# Dental_Support.net
KiCad netlist of a schematic drawn in Altium Designer
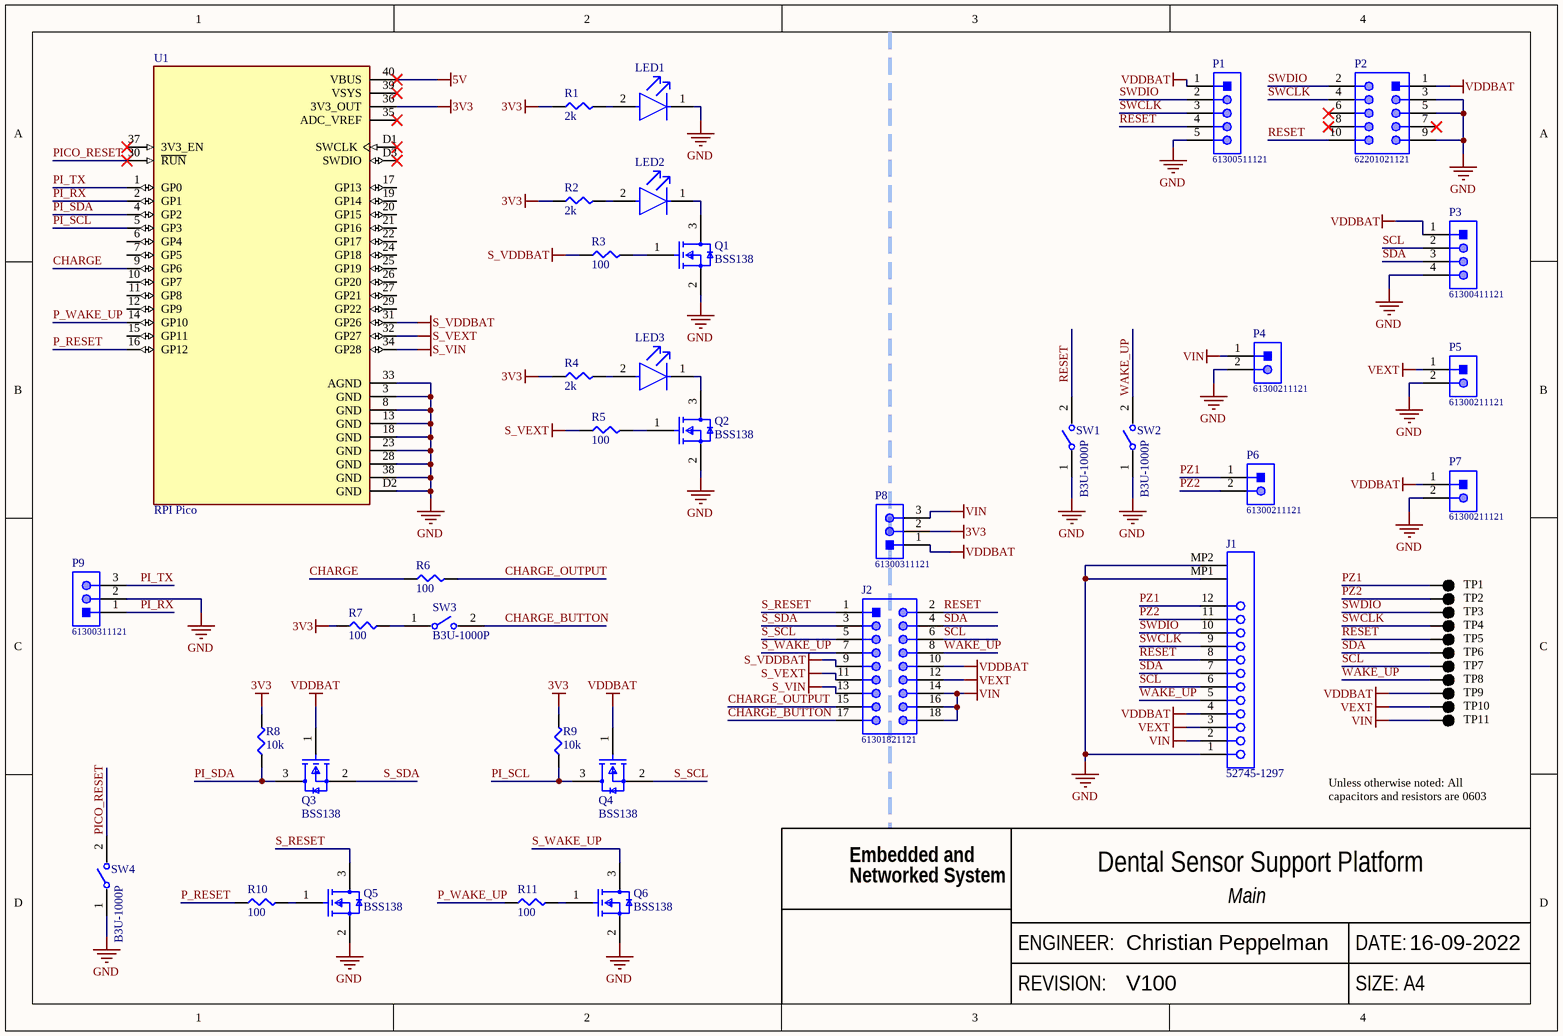
[diagram p0: Dental Support.SchDoc]

(export (version "E")
  (design (tool "Eeschema 10.0.6"))
  (components
    (comp (ref "J1")
      (value "52745-1297")
      (footprint "MOLX-52745-1297")
      (fields (field (name "MANUFACTURER") "Molex"))
      (libsource (lib "Altium Content Vault") (part "MOLX-52745-1297"))
    )
    (comp (ref "J2")
      (value "61301821121")
      (footprint "61301821121")
      (description "THT Vertical Pin Header WR-PHD, Pitch 2.54 mm, Dual Row, 18 pins")
      (fields (field (name "MANUFACTURER") "Wurth Elektronik") (field (name "PUBLISHER") "WurthElektronik"))
      (libsource (lib "Altium Content Vault") (part "WE-CN-2P-M-R18"))
    )
    (comp (ref "LED1")
      (value "150080SS75000")
      (footprint "FP-150080SS75000-MFG")
      (description "LED RED CLEAR 0805 SMD")
      (libsource (lib "Altium Content Vault") (part "8706943c75ba83719d021d2fdc84c58"))
    )
    (comp (ref "LED2")
      (value "150080SS75000")
      (footprint "FP-150080SS75000-MFG")
      (description "LED RED CLEAR 0805 SMD")
      (libsource (lib "Altium Content Vault") (part "8706943c75ba83719d021d2fdc84c58"))
    )
    (comp (ref "LED3")
      (value "150080SS75000")
      (footprint "FP-150080SS75000-MFG")
      (description "LED RED CLEAR 0805 SMD")
      (libsource (lib "Altium Content Vault") (part "8706943c75ba83719d021d2fdc84c58"))
    )
    (comp (ref "P1")
      (value "61300511121")
      (footprint "61300511121")
      (description "THT Vertical Pin Header WR-PHD, Pitch 2.54 mm, Single Row, 5 pins")
      (fields (field (name "MANUFACTURER") "Wurth Elektronik") (field (name "PUBLISHER") "WurthElektronik"))
      (libsource (lib "Altium Content Vault") (part "WE-CN-1P-M-R5"))
    )
    (comp (ref "P2")
      (value "62201021121")
      (footprint "62201021121")
      (description "THT Vertical Pin Header WR-PHD, Pitch 1.27 mm, Dual Row, 10 pins")
      (fields (field (name "MANUFACTURER") "Wurth Elektronik") (field (name "PUBLISHER") "WurthElektronik"))
      (libsource (lib "Altium Content Vault") (part "WE-CN-2P-M-R10"))
    )
    (comp (ref "P3")
      (value "61300411121")
      (footprint "61300411121")
      (description "THT Vertical Pin Header WR-PHD, Pitch 2.54 mm, Single Row, 4 pins")
      (fields (field (name "MANUFACTURER") "Wurth Elektronik") (field (name "PUBLISHER") "WurthElektronik"))
      (libsource (lib "Altium Content Vault") (part "WE-CN-1P-M-R4"))
    )
    (comp (ref "P4")
      (value "61300211121")
      (footprint "61300211121")
      (description "THT Vertical Pin Header WR-PHD, Pitch 2.54 mm, Single Row, 2 pins")
      (fields (field (name "MANUFACTURER") "Wurth Elektronik") (field (name "PUBLISHER") "WurthElektronik"))
      (libsource (lib "Altium Content Vault") (part "WE-CN-1P-M-R2"))
    )
    (comp (ref "P5")
      (value "61300211121")
      (footprint "61300211121")
      (description "THT Vertical Pin Header WR-PHD, Pitch 2.54 mm, Single Row, 2 pins")
      (fields (field (name "MANUFACTURER") "Wurth Elektronik") (field (name "PUBLISHER") "WurthElektronik"))
      (libsource (lib "Altium Content Vault") (part "WE-CN-1P-M-R2"))
    )
    (comp (ref "P6")
      (value "61300211121")
      (footprint "61300211121")
      (description "THT Vertical Pin Header WR-PHD, Pitch 2.54 mm, Single Row, 2 pins")
      (fields (field (name "MANUFACTURER") "Wurth Elektronik") (field (name "PUBLISHER") "WurthElektronik"))
      (libsource (lib "Altium Content Vault") (part "WE-CN-1P-M-R2"))
    )
    (comp (ref "P7")
      (value "61300211121")
      (footprint "61300211121")
      (description "THT Vertical Pin Header WR-PHD, Pitch 2.54 mm, Single Row, 2 pins")
      (fields (field (name "MANUFACTURER") "Wurth Elektronik") (field (name "PUBLISHER") "WurthElektronik"))
      (libsource (lib "Altium Content Vault") (part "WE-CN-1P-M-R2"))
    )
    (comp (ref "P8")
      (value "61300311121")
      (footprint "61300311121")
      (description "THT Vertical Pin Header WR-PHD, Pitch 2.54 mm, Single Row, 3 pins")
      (fields (field (name "MANUFACTURER") "Wurth Elektronik") (field (name "PUBLISHER") "WurthElektronik"))
      (libsource (lib "Altium Content Vault") (part "WE-CN-1P-M-R3"))
    )
    (comp (ref "P9")
      (value "61300311121")
      (footprint "61300311121")
      (description "THT Vertical Pin Header WR-PHD, Pitch 2.54 mm, Single Row, 3 pins")
      (fields (field (name "MANUFACTURER") "Wurth Elektronik") (field (name "PUBLISHER") "WurthElektronik"))
      (libsource (lib "Altium Content Vault") (part "WE-CN-1P-M-R3"))
    )
    (comp (ref "Q1")
      (value "BSS138")
      (footprint "FP-318-08-IPC_B")
      (description "MOSFET N-CH 50V 220MA SOT-23")
      (libsource (lib "Altium Content Vault") (part "3b9c635fedb024a5347a57b145af9cc"))
    )
    (comp (ref "Q2")
      (value "BSS138")
      (footprint "FP-318-08-IPC_B")
      (description "MOSFET N-CH 50V 220MA SOT-23")
      (libsource (lib "Altium Content Vault") (part "3b9c635fedb024a5347a57b145af9cc"))
    )
    (comp (ref "Q3")
      (value "BSS138")
      (footprint "FP-318-08-IPC_B")
      (description "MOSFET N-CH 50V 220MA SOT-23")
      (libsource (lib "Altium Content Vault") (part "3b9c635fedb024a5347a57b145af9cc"))
    )
    (comp (ref "Q4")
      (value "BSS138")
      (footprint "FP-318-08-IPC_B")
      (description "MOSFET N-CH 50V 220MA SOT-23")
      (libsource (lib "Altium Content Vault") (part "3b9c635fedb024a5347a57b145af9cc"))
    )
    (comp (ref "Q5")
      (value "BSS138")
      (footprint "FP-318-08-IPC_B")
      (description "MOSFET N-CH 50V 220MA SOT-23")
      (libsource (lib "Altium Content Vault") (part "3b9c635fedb024a5347a57b145af9cc"))
    )
    (comp (ref "Q6")
      (value "BSS138")
      (footprint "FP-318-08-IPC_B")
      (description "MOSFET N-CH 50V 220MA SOT-23")
      (libsource (lib "Altium Content Vault") (part "3b9c635fedb024a5347a57b145af9cc"))
    )
    (comp (ref "R1")
      (value "2k")
      (footprint "RESC2012X06N")
      (description "RES SMD 2K OHM 1% 1/8W 0805")
      (fields
        (field (name "PART NUMBER") "ERJ-6ENF2001V")
        (field (name "DIGI-KEY PART NUMBER") "P2.00KCCT-ND")
      )
      (libsource (lib "Panasonic_ERJ_0805") (part "ERJ-6ENF2001V"))
    )
    (comp (ref "R2")
      (value "2k")
      (footprint "RESC2012X06N")
      (description "RES SMD 2K OHM 1% 1/8W 0805")
      (fields
        (field (name "PART NUMBER") "ERJ-6ENF2001V")
        (field (name "DIGI-KEY PART NUMBER") "P2.00KCCT-ND")
      )
      (libsource (lib "Panasonic_ERJ_0805") (part "ERJ-6ENF2001V"))
    )
    (comp (ref "R3")
      (value "100")
      (footprint "RESC2012X06N")
      (description "RES SMD 100 OHM 1% 1/8W 0805")
      (fields (field (name "PART NUMBER") "ERJ-6ENF1000V") (field (name "DIGI-KEY PART NUMBER") "P100CCT-ND"))
      (libsource (lib "Panasonic_ERJ_0805") (part "ERJ-6ENF1000V"))
    )
    (comp (ref "R4")
      (value "2k")
      (footprint "RESC2012X06N")
      (description "RES SMD 2K OHM 1% 1/8W 0805")
      (fields
        (field (name "PART NUMBER") "ERJ-6ENF2001V")
        (field (name "DIGI-KEY PART NUMBER") "P2.00KCCT-ND")
      )
      (libsource (lib "Panasonic_ERJ_0805") (part "ERJ-6ENF2001V"))
    )
    (comp (ref "R5")
      (value "100")
      (footprint "RESC2012X06N")
      (description "RES SMD 100 OHM 1% 1/8W 0805")
      (fields (field (name "PART NUMBER") "ERJ-6ENF1000V") (field (name "DIGI-KEY PART NUMBER") "P100CCT-ND"))
      (libsource (lib "Panasonic_ERJ_0805") (part "ERJ-6ENF1000V"))
    )
    (comp (ref "R6")
      (value "100")
      (footprint "RESC2012X06N")
      (description "RES SMD 100 OHM 1% 1/8W 0805")
      (fields (field (name "PART NUMBER") "ERJ-6ENF1000V") (field (name "DIGI-KEY PART NUMBER") "P100CCT-ND"))
      (libsource (lib "Panasonic_ERJ_0805") (part "ERJ-6ENF1000V"))
    )
    (comp (ref "R7")
      (value "100")
      (footprint "RESC2012X06N")
      (description "RES SMD 100 OHM 1% 1/8W 0805")
      (fields (field (name "PART NUMBER") "ERJ-6ENF1000V") (field (name "DIGI-KEY PART NUMBER") "P100CCT-ND"))
      (libsource (lib "Panasonic_ERJ_0805") (part "ERJ-6ENF1000V"))
    )
    (comp (ref "R8")
      (value "10k")
      (footprint "RESC2012X06N")
      (description "RES SMD 10K OHM 1% 1/8W 0805")
      (fields
        (field (name "PART NUMBER") "ERJ-6ENF1002V")
        (field (name "DIGI-KEY PART NUMBER") "P10.0KCCT-ND")
      )
      (libsource (lib "Panasonic_ERJ_0805") (part "ERJ-6ENF1002V"))
    )
    (comp (ref "R9")
      (value "10k")
      (footprint "RESC2012X06N")
      (description "RES SMD 10K OHM 1% 1/8W 0805")
      (fields
        (field (name "PART NUMBER") "ERJ-6ENF1002V")
        (field (name "DIGI-KEY PART NUMBER") "P10.0KCCT-ND")
      )
      (libsource (lib "Panasonic_ERJ_0805") (part "ERJ-6ENF1002V"))
    )
    (comp (ref "R10")
      (value "100")
      (footprint "RESC2012X06N")
      (description "RES SMD 100 OHM 1% 1/8W 0805")
      (fields (field (name "PART NUMBER") "ERJ-6ENF1000V") (field (name "DIGI-KEY PART NUMBER") "P100CCT-ND"))
      (libsource (lib "Panasonic_ERJ_0805") (part "ERJ-6ENF1000V"))
    )
    (comp (ref "R11")
      (value "100")
      (footprint "RESC2012X06N")
      (description "RES SMD 100 OHM 1% 1/8W 0805")
      (fields (field (name "PART NUMBER") "ERJ-6ENF1000V") (field (name "DIGI-KEY PART NUMBER") "P100CCT-ND"))
      (libsource (lib "Panasonic_ERJ_0805") (part "ERJ-6ENF1000V"))
    )
    (comp (ref "SW1")
      (value "B3U-1000P")
      (footprint "FP-B3U-1000P-MFG")
      (description "SWITCH TACTILE SPST-NO 0.05A 12V")
      (libsource (lib "Altium Content Vault") (part "ae622034201233ca1abcedc05908f33"))
    )
    (comp (ref "SW2")
      (value "B3U-1000P")
      (footprint "FP-B3U-1000P-MFG")
      (description "SWITCH TACTILE SPST-NO 0.05A 12V")
      (libsource (lib "Altium Content Vault") (part "ae622034201233ca1abcedc05908f33"))
    )
    (comp (ref "SW3")
      (value "B3U-1000P")
      (footprint "FP-B3U-1000P-MFG")
      (description "SWITCH TACTILE SPST-NO 0.05A 12V")
      (libsource (lib "Altium Content Vault") (part "ae622034201233ca1abcedc05908f33"))
    )
    (comp (ref "SW4")
      (value "B3U-1000P")
      (footprint "FP-B3U-1000P-MFG")
      (description "SWITCH TACTILE SPST-NO 0.05A 12V")
      (libsource (lib "Altium Content Vault") (part "ae622034201233ca1abcedc05908f33"))
    )
    (comp (ref "TP1")
      (value "5011")
      (footprint "KSTN-5011_V")
      (description "Test Point, Black, Through Hole, RoHS, Bulk")
      (fields (field (name "MANUFACTURER") "Keystone"))
      (libsource (lib "Altium Content Vault") (part "TESTPOINT_BLACK"))
    )
    (comp (ref "TP2")
      (value "5011")
      (footprint "KSTN-5011_V")
      (description "Test Point, Black, Through Hole, RoHS, Bulk")
      (fields (field (name "MANUFACTURER") "Keystone"))
      (libsource (lib "Altium Content Vault") (part "TESTPOINT_BLACK"))
    )
    (comp (ref "TP3")
      (value "5011")
      (footprint "KSTN-5011_V")
      (description "Test Point, Black, Through Hole, RoHS, Bulk")
      (fields (field (name "MANUFACTURER") "Keystone"))
      (libsource (lib "Altium Content Vault") (part "TESTPOINT_BLACK"))
    )
    (comp (ref "TP4")
      (value "5011")
      (footprint "KSTN-5011_V")
      (description "Test Point, Black, Through Hole, RoHS, Bulk")
      (fields (field (name "MANUFACTURER") "Keystone"))
      (libsource (lib "Altium Content Vault") (part "TESTPOINT_BLACK"))
    )
    (comp (ref "TP5")
      (value "5011")
      (footprint "KSTN-5011_V")
      (description "Test Point, Black, Through Hole, RoHS, Bulk")
      (fields (field (name "MANUFACTURER") "Keystone"))
      (libsource (lib "Altium Content Vault") (part "TESTPOINT_BLACK"))
    )
    (comp (ref "TP6")
      (value "5011")
      (footprint "KSTN-5011_V")
      (description "Test Point, Black, Through Hole, RoHS, Bulk")
      (fields (field (name "MANUFACTURER") "Keystone"))
      (libsource (lib "Altium Content Vault") (part "TESTPOINT_BLACK"))
    )
    (comp (ref "TP7")
      (value "5011")
      (footprint "KSTN-5011_V")
      (description "Test Point, Black, Through Hole, RoHS, Bulk")
      (fields (field (name "MANUFACTURER") "Keystone"))
      (libsource (lib "Altium Content Vault") (part "TESTPOINT_BLACK"))
    )
    (comp (ref "TP8")
      (value "5011")
      (footprint "KSTN-5011_V")
      (description "Test Point, Black, Through Hole, RoHS, Bulk")
      (fields (field (name "MANUFACTURER") "Keystone"))
      (libsource (lib "Altium Content Vault") (part "TESTPOINT_BLACK"))
    )
    (comp (ref "TP9")
      (value "5011")
      (footprint "KSTN-5011_V")
      (description "Test Point, Black, Through Hole, RoHS, Bulk")
      (fields (field (name "MANUFACTURER") "Keystone"))
      (libsource (lib "Altium Content Vault") (part "TESTPOINT_BLACK"))
    )
    (comp (ref "TP10")
      (value "5011")
      (footprint "KSTN-5011_V")
      (description "Test Point, Black, Through Hole, RoHS, Bulk")
      (fields (field (name "MANUFACTURER") "Keystone"))
      (libsource (lib "Altium Content Vault") (part "TESTPOINT_BLACK"))
    )
    (comp (ref "TP11")
      (value "5011")
      (footprint "KSTN-5011_V")
      (description "Test Point, Black, Through Hole, RoHS, Bulk")
      (fields (field (name "MANUFACTURER") "Keystone"))
      (libsource (lib "Altium Content Vault") (part "TESTPOINT_BLACK"))
    )
    (comp (ref "U1") (value "RPI Pico") (footprint "RPI Pico") (libsource (lib "Library") (part "RPI Pico")))
  )
  (nets
    (net (code "1") (name "/CHARGE") (class "Default")
      (node (ref "R6") (pin "1") (pinfunction "1_1") (pintype "passive"))
      (node (ref "U1") (pin "9") (pinfunction "GP6_9") (pintype "bidirectional"))
    )
    (net (code "2") (name "/CHARGE_BUTTON") (class "Default")
      (node (ref "J2") (pin "17") (pinfunction "17_17") (pintype "passive"))
      (node (ref "SW3") (pin "2") (pinfunction "2_2") (pintype "passive"))
    )
    (net (code "3") (name "/CHARGE_OUTPUT") (class "Default")
      (node (ref "J2") (pin "15") (pinfunction "15_15") (pintype "passive"))
      (node (ref "R6") (pin "2") (pinfunction "2_2") (pintype "passive"))
    )
    (net (code "4") (name "/PICO_RESET") (class "Default")
      (node (ref "SW4") (pin "2") (pinfunction "2_2") (pintype "passive"))
      (node (ref "U1") (pin "30") (pinfunction "~{RUN}_30") (pintype "input"))
    )
    (net (code "5") (name "/PI_RX") (class "Default")
      (node (ref "P9") (pin "1") (pinfunction "1_1") (pintype "passive"))
      (node (ref "U1") (pin "2") (pinfunction "GP1_2") (pintype "bidirectional"))
    )
    (net (code "6") (name "/PI_SCL") (class "Default")
      (node (ref "Q4") (pin "3") (pinfunction "D_3") (pintype "passive"))
      (node (ref "R9") (pin "1") (pinfunction "1_1") (pintype "passive"))
      (node (ref "U1") (pin "5") (pinfunction "GP3_5") (pintype "bidirectional"))
    )
    (net (code "7") (name "/PI_SDA") (class "Default")
      (node (ref "Q3") (pin "3") (pinfunction "D_3") (pintype "passive"))
      (node (ref "R8") (pin "1") (pinfunction "1_1") (pintype "passive"))
      (node (ref "U1") (pin "4") (pinfunction "GP2_4") (pintype "bidirectional"))
    )
    (net (code "8") (name "/PI_TX") (class "Default")
      (node (ref "P9") (pin "3") (pinfunction "3_3") (pintype "passive"))
      (node (ref "U1") (pin "1") (pinfunction "GP0_1") (pintype "bidirectional"))
    )
    (net (code "9") (name "/PZ1") (class "Default")
      (node (ref "J1") (pin "12") (pinfunction "12_12") (pintype "passive"))
      (node (ref "P6") (pin "1") (pinfunction "1_1") (pintype "passive"))
      (node (ref "TP1") (pin "1") (pinfunction "1_1") (pintype "passive"))
    )
    (net (code "10") (name "/PZ2") (class "Default")
      (node (ref "J1") (pin "11") (pinfunction "11_11") (pintype "passive"))
      (node (ref "P6") (pin "2") (pinfunction "2_2") (pintype "passive"))
      (node (ref "TP2") (pin "1") (pinfunction "1_1") (pintype "passive"))
    )
    (net (code "11") (name "/P_RESET") (class "Default")
      (node (ref "R10") (pin "1") (pinfunction "1_1") (pintype "passive"))
      (node (ref "U1") (pin "16") (pinfunction "GP12_16") (pintype "bidirectional"))
    )
    (net (code "12") (name "/P_WAKE_UP") (class "Default")
      (node (ref "R11") (pin "1") (pinfunction "1_1") (pintype "passive"))
      (node (ref "U1") (pin "14") (pinfunction "GP10_14") (pintype "bidirectional"))
    )
    (net (code "13") (name "/RESET") (class "Default")
      (node (ref "J1") (pin "8") (pinfunction "8_8") (pintype "passive"))
      (node (ref "J2") (pin "2") (pinfunction "2_2") (pintype "passive"))
      (node (ref "P1") (pin "4") (pinfunction "4_4") (pintype "passive"))
      (node (ref "P2") (pin "10") (pinfunction "10_10") (pintype "passive"))
      (node (ref "SW1") (pin "2") (pinfunction "2_2") (pintype "passive"))
      (node (ref "TP5") (pin "1") (pinfunction "1_1") (pintype "passive"))
    )
    (net (code "14") (name "/SCL") (class "Default")
      (node (ref "J1") (pin "6") (pinfunction "6_6") (pintype "passive"))
      (node (ref "J2") (pin "6") (pinfunction "6_6") (pintype "passive"))
      (node (ref "P3") (pin "2") (pinfunction "2_2") (pintype "passive"))
      (node (ref "TP7") (pin "1") (pinfunction "1_1") (pintype "passive"))
    )
    (net (code "15") (name "/SDA") (class "Default")
      (node (ref "J1") (pin "7") (pinfunction "7_7") (pintype "passive"))
      (node (ref "J2") (pin "4") (pinfunction "4_4") (pintype "passive"))
      (node (ref "P3") (pin "3") (pinfunction "3_3") (pintype "passive"))
      (node (ref "TP6") (pin "1") (pinfunction "1_1") (pintype "passive"))
    )
    (net (code "16") (name "/SWCLK") (class "Default")
      (node (ref "J1") (pin "9") (pinfunction "9_9") (pintype "passive"))
      (node (ref "P1") (pin "3") (pinfunction "3_3") (pintype "passive"))
      (node (ref "P2") (pin "4") (pinfunction "4_4") (pintype "passive"))
      (node (ref "TP4") (pin "1") (pinfunction "1_1") (pintype "passive"))
    )
    (net (code "17") (name "/SWDIO") (class "Default")
      (node (ref "J1") (pin "10") (pinfunction "10_10") (pintype "passive"))
      (node (ref "P1") (pin "2") (pinfunction "2_2") (pintype "passive"))
      (node (ref "P2") (pin "2") (pinfunction "2_2") (pintype "passive"))
      (node (ref "TP3") (pin "1") (pinfunction "1_1") (pintype "passive"))
    )
    (net (code "18") (name "/S_RESET") (class "Default")
      (node (ref "J2") (pin "1") (pinfunction "1_1") (pintype "passive"))
      (node (ref "Q5") (pin "3") (pinfunction "D_3") (pintype "passive"))
    )
    (net (code "19") (name "/S_SCL") (class "Default")
      (node (ref "J2") (pin "5") (pinfunction "5_5") (pintype "passive"))
      (node (ref "Q4") (pin "2") (pinfunction "S_2") (pintype "passive"))
    )
    (net (code "20") (name "/S_SDA") (class "Default")
      (node (ref "J2") (pin "3") (pinfunction "3_3") (pintype "passive"))
      (node (ref "Q3") (pin "2") (pinfunction "S_2") (pintype "passive"))
    )
    (net (code "21") (name "/S_WAKE_UP") (class "Default")
      (node (ref "J2") (pin "7") (pinfunction "7_7") (pintype "passive"))
      (node (ref "Q6") (pin "3") (pinfunction "D_3") (pintype "passive"))
    )
    (net (code "22") (name "/WAKE_UP") (class "Default")
      (node (ref "J1") (pin "5") (pinfunction "5_5") (pintype "passive"))
      (node (ref "J2") (pin "8") (pinfunction "8_8") (pintype "passive"))
      (node (ref "SW2") (pin "2") (pinfunction "2_2") (pintype "passive"))
      (node (ref "TP8") (pin "1") (pinfunction "1_1") (pintype "passive"))
    )
    (net (code "23") (name "3V3") (class "Default")
      (node (ref "P8") (pin "2") (pinfunction "2_2") (pintype "passive"))
      (node (ref "R1") (pin "1") (pinfunction "1_1") (pintype "passive"))
      (node (ref "R2") (pin "1") (pinfunction "1_1") (pintype "passive"))
      (node (ref "R4") (pin "1") (pinfunction "1_1") (pintype "passive"))
      (node (ref "R7") (pin "1") (pinfunction "1_1") (pintype "passive"))
      (node (ref "R8") (pin "2") (pinfunction "2_2") (pintype "passive"))
      (node (ref "R9") (pin "2") (pinfunction "2_2") (pintype "passive"))
      (node (ref "U1") (pin "36") (pinfunction "3V3_OUT_36") (pintype "power_in"))
    )
    (net (code "24") (name "5V") (class "Default")
      (node (ref "U1") (pin "40") (pinfunction "VBUS_40") (pintype "power_in"))
    )
    (net (code "25") (name "GND") (class "Default")
      (node (ref "J1") (pin "1") (pinfunction "1_1") (pintype "passive"))
      (node (ref "J1") (pin "MP1") (pinfunction "MP1_MP1") (pintype "passive"))
      (node (ref "J1") (pin "MP2") (pinfunction "MP2_MP2") (pintype "passive"))
      (node (ref "LED1") (pin "1") (pinfunction "C_1") (pintype "passive"))
      (node (ref "P1") (pin "5") (pinfunction "5_5") (pintype "passive"))
      (node (ref "P2") (pin "3") (pinfunction "3_3") (pintype "passive"))
      (node (ref "P2") (pin "5") (pinfunction "5_5") (pintype "passive"))
      (node (ref "P2") (pin "9") (pinfunction "9_9") (pintype "passive"))
      (node (ref "P3") (pin "4") (pinfunction "4_4") (pintype "passive"))
      (node (ref "P4") (pin "2") (pinfunction "2_2") (pintype "passive"))
      (node (ref "P5") (pin "2") (pinfunction "2_2") (pintype "passive"))
      (node (ref "P7") (pin "2") (pinfunction "2_2") (pintype "passive"))
      (node (ref "P9") (pin "2") (pinfunction "2_2") (pintype "passive"))
      (node (ref "Q1") (pin "2") (pinfunction "S_2") (pintype "passive"))
      (node (ref "Q2") (pin "2") (pinfunction "S_2") (pintype "passive"))
      (node (ref "Q5") (pin "2") (pinfunction "S_2") (pintype "passive"))
      (node (ref "Q6") (pin "2") (pinfunction "S_2") (pintype "passive"))
      (node (ref "SW1") (pin "1") (pinfunction "1_1") (pintype "passive"))
      (node (ref "SW2") (pin "1") (pinfunction "1_1") (pintype "passive"))
      (node (ref "SW4") (pin "1") (pinfunction "1_1") (pintype "passive"))
      (node (ref "U1") (pin "13") (pinfunction "GND_13") (pintype "power_in"))
      (node (ref "U1") (pin "18") (pinfunction "GND_18") (pintype "power_in"))
      (node (ref "U1") (pin "23") (pinfunction "GND_23") (pintype "power_in"))
      (node (ref "U1") (pin "28") (pinfunction "GND_28") (pintype "power_in"))
      (node (ref "U1") (pin "3") (pinfunction "GND_3") (pintype "power_in"))
      (node (ref "U1") (pin "33") (pinfunction "AGND_33") (pintype "power_in"))
      (node (ref "U1") (pin "38") (pinfunction "GND_38") (pintype "power_in"))
      (node (ref "U1") (pin "8") (pinfunction "GND_8") (pintype "power_in"))
      (node (ref "U1") (pin "D2") (pinfunction "GND_D2") (pintype "power_in"))
    )
    (net (code "26") (name "Net-(LED1-A)") (class "Default")
      (node (ref "LED1") (pin "2") (pinfunction "A_2") (pintype "passive"))
      (node (ref "R1") (pin "2") (pinfunction "2_2") (pintype "passive"))
    )
    (net (code "27") (name "Net-(LED2-A)") (class "Default")
      (node (ref "LED2") (pin "2") (pinfunction "A_2") (pintype "passive"))
      (node (ref "R2") (pin "2") (pinfunction "2_2") (pintype "passive"))
    )
    (net (code "28") (name "Net-(LED2-C)") (class "Default")
      (node (ref "LED2") (pin "1") (pinfunction "C_1") (pintype "passive"))
      (node (ref "Q1") (pin "3") (pinfunction "D_3") (pintype "passive"))
    )
    (net (code "29") (name "Net-(LED3-A)") (class "Default")
      (node (ref "LED3") (pin "2") (pinfunction "A_2") (pintype "passive"))
      (node (ref "R4") (pin "2") (pinfunction "2_2") (pintype "passive"))
    )
    (net (code "30") (name "Net-(LED3-C)") (class "Default")
      (node (ref "LED3") (pin "1") (pinfunction "C_1") (pintype "passive"))
      (node (ref "Q2") (pin "3") (pinfunction "D_3") (pintype "passive"))
    )
    (net (code "31") (name "Net-(Q1-G)") (class "Default")
      (node (ref "Q1") (pin "1") (pinfunction "G_1") (pintype "passive"))
      (node (ref "R3") (pin "2") (pinfunction "2_2") (pintype "passive"))
    )
    (net (code "32") (name "Net-(Q2-G)") (class "Default")
      (node (ref "Q2") (pin "1") (pinfunction "G_1") (pintype "passive"))
      (node (ref "R5") (pin "2") (pinfunction "2_2") (pintype "passive"))
    )
    (net (code "33") (name "Net-(Q5-G)") (class "Default")
      (node (ref "Q5") (pin "1") (pinfunction "G_1") (pintype "passive"))
      (node (ref "R10") (pin "2") (pinfunction "2_2") (pintype "passive"))
    )
    (net (code "34") (name "Net-(Q6-G)") (class "Default")
      (node (ref "Q6") (pin "1") (pinfunction "G_1") (pintype "passive"))
      (node (ref "R11") (pin "2") (pinfunction "2_2") (pintype "passive"))
    )
    (net (code "35") (name "Net-(R7-Pad2)") (class "Default")
      (node (ref "R7") (pin "2") (pinfunction "2_2") (pintype "passive"))
      (node (ref "SW3") (pin "1") (pinfunction "1_1") (pintype "passive"))
    )
    (net (code "36") (name "S_VDDBAT") (class "Default")
      (node (ref "J2") (pin "9") (pinfunction "9_9") (pintype "passive"))
      (node (ref "R3") (pin "1") (pinfunction "1_1") (pintype "passive"))
      (node (ref "U1") (pin "31") (pinfunction "GP26_31") (pintype "bidirectional"))
    )
    (net (code "37") (name "S_VEXT") (class "Default")
      (node (ref "J2") (pin "11") (pinfunction "11_11") (pintype "passive"))
      (node (ref "R5") (pin "1") (pinfunction "1_1") (pintype "passive"))
      (node (ref "U1") (pin "32") (pinfunction "GP27_32") (pintype "bidirectional"))
    )
    (net (code "38") (name "S_VIN") (class "Default")
      (node (ref "J2") (pin "13") (pinfunction "13_13") (pintype "passive"))
      (node (ref "U1") (pin "34") (pinfunction "GP28_34") (pintype "bidirectional"))
    )
    (net (code "39") (name "VDDBAT") (class "Default")
      (node (ref "J1") (pin "4") (pinfunction "4_4") (pintype "passive"))
      (node (ref "J2") (pin "10") (pinfunction "10_10") (pintype "passive"))
      (node (ref "P1") (pin "1") (pinfunction "1_1") (pintype "passive"))
      (node (ref "P2") (pin "1") (pinfunction "1_1") (pintype "passive"))
      (node (ref "P3") (pin "1") (pinfunction "1_1") (pintype "passive"))
      (node (ref "P7") (pin "1") (pinfunction "1_1") (pintype "passive"))
      (node (ref "P8") (pin "1") (pinfunction "1_1") (pintype "passive"))
      (node (ref "Q3") (pin "1") (pinfunction "G_1") (pintype "passive"))
      (node (ref "Q4") (pin "1") (pinfunction "G_1") (pintype "passive"))
      (node (ref "TP9") (pin "1") (pinfunction "1_1") (pintype "passive"))
    )
    (net (code "40") (name "VEXT") (class "Default")
      (node (ref "J1") (pin "3") (pinfunction "3_3") (pintype "passive"))
      (node (ref "J2") (pin "12") (pinfunction "12_12") (pintype "passive"))
      (node (ref "P5") (pin "1") (pinfunction "1_1") (pintype "passive"))
      (node (ref "TP10") (pin "1") (pinfunction "1_1") (pintype "passive"))
    )
    (net (code "41") (name "VIN") (class "Default")
      (node (ref "J1") (pin "2") (pinfunction "2_2") (pintype "passive"))
      (node (ref "J2") (pin "14") (pinfunction "14_14") (pintype "passive"))
      (node (ref "J2") (pin "16") (pinfunction "16_16") (pintype "passive"))
      (node (ref "J2") (pin "18") (pinfunction "18_18") (pintype "passive"))
      (node (ref "P4") (pin "1") (pinfunction "1_1") (pintype "passive"))
      (node (ref "P8") (pin "3") (pinfunction "3_3") (pintype "passive"))
      (node (ref "TP11") (pin "1") (pinfunction "1_1") (pintype "passive"))
    )
    (net (code "42") (name "unconnected-(P2-Pad6)") (class "Default")
      (node (ref "P2") (pin "6") (pinfunction "6_6") (pintype "passive+no_connect"))
    )
    (net (code "43") (name "unconnected-(P2-Pad7)") (class "Default")
      (node (ref "P2") (pin "7") (pinfunction "7_7") (pintype "passive+no_connect"))
    )
    (net (code "44") (name "unconnected-(P2-Pad8)") (class "Default")
      (node (ref "P2") (pin "8") (pinfunction "8_8") (pintype "passive+no_connect"))
    )
    (net (code "45") (name "unconnected-(U1-3V3_EN-Pad37)") (class "Default")
      (node (ref "U1") (pin "37") (pinfunction "3V3_EN_37") (pintype "input+no_connect"))
    )
    (net (code "46") (name "unconnected-(U1-ADC_VREF-Pad35)") (class "Default")
      (node (ref "U1") (pin "35") (pinfunction "ADC_VREF_35") (pintype "power_in+no_connect"))
    )
    (net (code "47") (name "unconnected-(U1-GP4-Pad6)") (class "Default")
      (node (ref "U1") (pin "6") (pinfunction "GP4_6") (pintype "bidirectional"))
    )
    (net (code "48") (name "unconnected-(U1-GP5-Pad7)") (class "Default")
      (node (ref "U1") (pin "7") (pinfunction "GP5_7") (pintype "bidirectional"))
    )
    (net (code "49") (name "unconnected-(U1-GP7-Pad10)") (class "Default")
      (node (ref "U1") (pin "10") (pinfunction "GP7_10") (pintype "bidirectional"))
    )
    (net (code "50") (name "unconnected-(U1-GP8-Pad11)") (class "Default")
      (node (ref "U1") (pin "11") (pinfunction "GP8_11") (pintype "bidirectional"))
    )
    (net (code "51") (name "unconnected-(U1-GP9-Pad12)") (class "Default")
      (node (ref "U1") (pin "12") (pinfunction "GP9_12") (pintype "bidirectional"))
    )
    (net (code "52") (name "unconnected-(U1-GP11-Pad15)") (class "Default")
      (node (ref "U1") (pin "15") (pinfunction "GP11_15") (pintype "bidirectional"))
    )
    (net (code "53") (name "unconnected-(U1-GP13-Pad17)") (class "Default")
      (node (ref "U1") (pin "17") (pinfunction "GP13_17") (pintype "bidirectional"))
    )
    (net (code "54") (name "unconnected-(U1-GP14-Pad19)") (class "Default")
      (node (ref "U1") (pin "19") (pinfunction "GP14_19") (pintype "bidirectional"))
    )
    (net (code "55") (name "unconnected-(U1-GP15-Pad20)") (class "Default")
      (node (ref "U1") (pin "20") (pinfunction "GP15_20") (pintype "bidirectional"))
    )
    (net (code "56") (name "unconnected-(U1-GP16-Pad21)") (class "Default")
      (node (ref "U1") (pin "21") (pinfunction "GP16_21") (pintype "bidirectional"))
    )
    (net (code "57") (name "unconnected-(U1-GP17-Pad22)") (class "Default")
      (node (ref "U1") (pin "22") (pinfunction "GP17_22") (pintype "bidirectional"))
    )
    (net (code "58") (name "unconnected-(U1-GP18-Pad24)") (class "Default")
      (node (ref "U1") (pin "24") (pinfunction "GP18_24") (pintype "bidirectional"))
    )
    (net (code "59") (name "unconnected-(U1-GP19-Pad25)") (class "Default")
      (node (ref "U1") (pin "25") (pinfunction "GP19_25") (pintype "bidirectional"))
    )
    (net (code "60") (name "unconnected-(U1-GP20-Pad26)") (class "Default")
      (node (ref "U1") (pin "26") (pinfunction "GP20_26") (pintype "bidirectional"))
    )
    (net (code "61") (name "unconnected-(U1-GP21-Pad27)") (class "Default")
      (node (ref "U1") (pin "27") (pinfunction "GP21_27") (pintype "bidirectional"))
    )
    (net (code "62") (name "unconnected-(U1-GP22-Pad29)") (class "Default")
      (node (ref "U1") (pin "29") (pinfunction "GP22_29") (pintype "bidirectional"))
    )
    (net (code "63") (name "unconnected-(U1-SWCLK-PadD1)") (class "Default")
      (node (ref "U1") (pin "D1") (pinfunction "SWCLK_D1") (pintype "input+no_connect"))
    )
    (net (code "64") (name "unconnected-(U1-SWDIO-PadD3)") (class "Default")
      (node (ref "U1") (pin "D3") (pinfunction "SWDIO_D3") (pintype "bidirectional+no_connect"))
    )
    (net (code "65") (name "unconnected-(U1-VSYS-Pad39)") (class "Default")
      (node (ref "U1") (pin "39") (pinfunction "VSYS_39") (pintype "power_in+no_connect"))
    )
  )
)
